# OZ440-SE100-CAR003_sheet8.net
KiCad netlist of a schematic drawn in Altium Designer
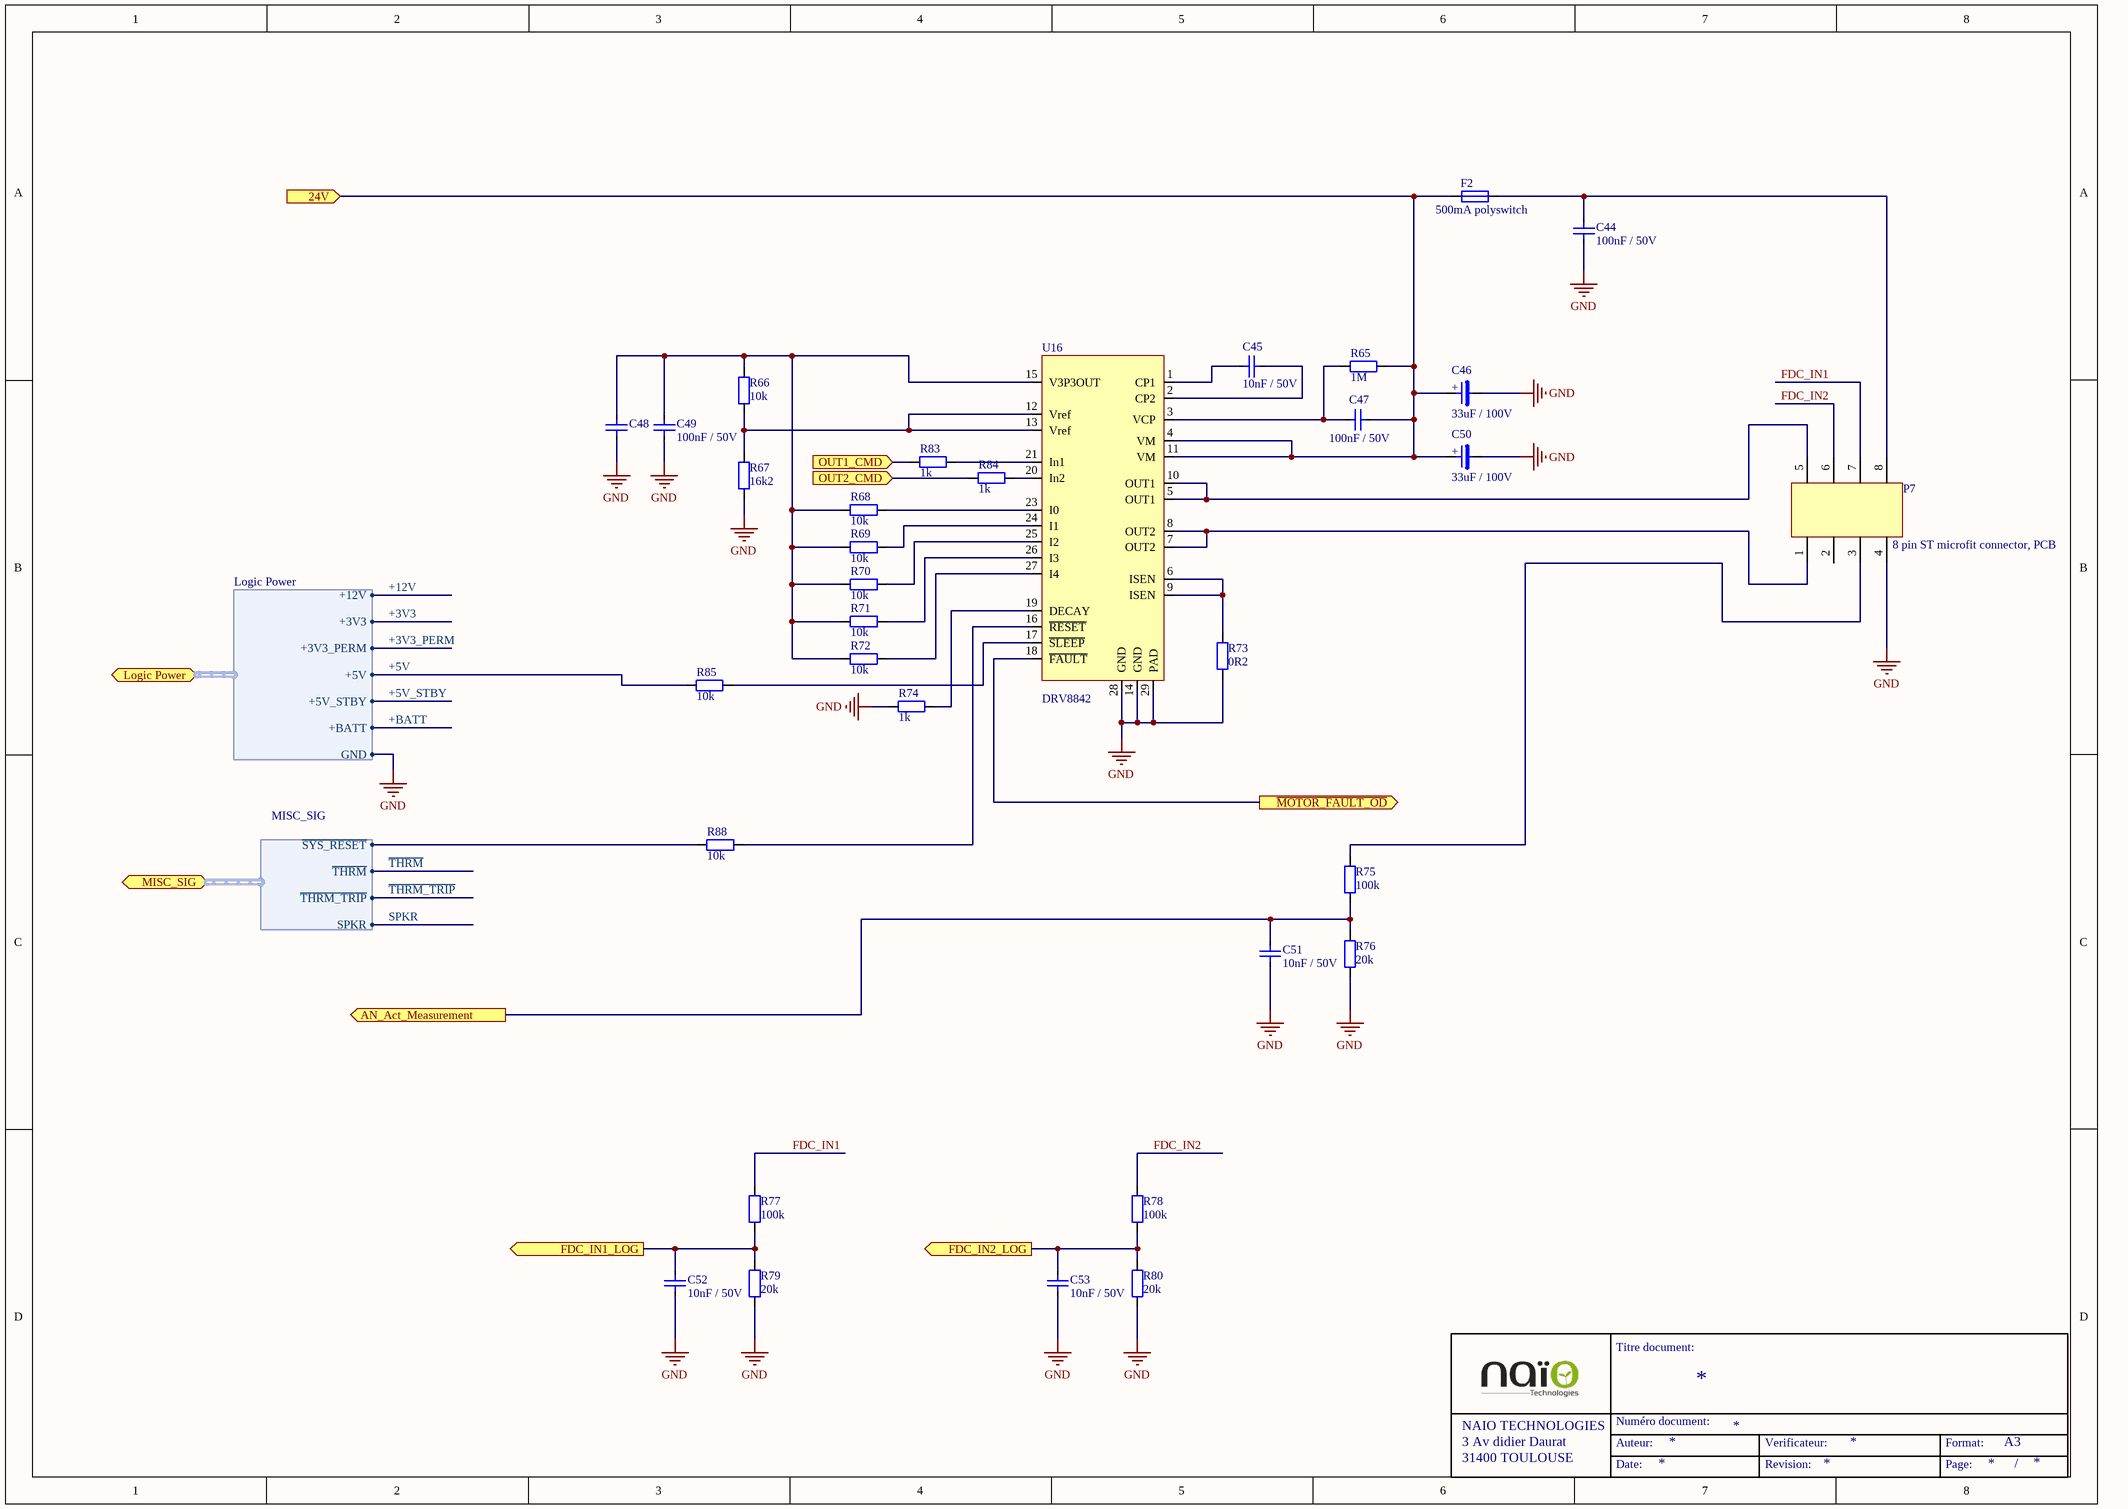
[diagram p0: OZ440-SE100-CAR003_sheet8.SchDoc]

(export (version "E")
  (design (tool "Eeschema 10.0.6"))
  (components
    (comp (ref "C44")
      (value "CAP-SMD")
      (footprint "C0805-STD")
      (description "0805 100nF / 50V  X7R ceramic capacitor")
      (fields
        (field (name "DISPLAYED REFERENCE") "100nF / 50V")
        (field (name "TOLERANCE") "+/- 10%")
        (field (name "MANUFACTURER") "vishay")
      )
      (libsource (lib "lib_NAIO") (part "CAP-SMD"))
    )
    (comp (ref "C45")
      (value "CAP-SMD")
      (footprint "C0805-STD")
      (description "0805 10nF / 50V X7R ceramic capacitor")
      (fields
        (field (name "DISPLAYED REFERENCE") "10nF / 50V")
        (field (name "TOLERANCE") "+/- 10%")
        (field (name "MANUFACTURER") "vishay")
      )
      (libsource (lib "lib_NAIO") (part "CAP-SMD"))
    )
    (comp (ref "C46")
      (value "CAP-POL-SMD")
      (footprint "CAP-ELECTRO-SMD_SIZE_G")
      (description "33uF / 100V Aluminium capacitor SMD")
      (fields (field (name "DISPLAYED REFERENCE") "33uF / 100V") (field (name "MANUFACTURER") "Panasonic"))
      (libsource (lib "lib_NAIO") (part "CAP-POL-SMD"))
    )
    (comp (ref "C47")
      (value "CAP-SMD")
      (footprint "C0805-STD")
      (description "0805 100nF / 50V  X7R ceramic capacitor")
      (fields
        (field (name "DISPLAYED REFERENCE") "100nF / 50V")
        (field (name "TOLERANCE") "+/- 10%")
        (field (name "MANUFACTURER") "vishay")
      )
      (libsource (lib "lib_NAIO") (part "CAP-SMD"))
    )
    (comp (ref "C48")
      (value "CAP-SMD")
      (footprint "C0805-STD")
      (description "0805 100nF / 50V  X7R ceramic capacitor")
      (fields (field (name "TOLERANCE") "+/- 10%") (field (name "MANUFACTURER") "vishay"))
      (libsource (lib "lib_NAIO") (part "CAP-SMD"))
    )
    (comp (ref "C49")
      (value "CAP-SMD")
      (footprint "C0805-STD")
      (description "0805 100nF / 50V  X7R ceramic capacitor")
      (fields
        (field (name "DISPLAYED REFERENCE") "100nF / 50V")
        (field (name "TOLERANCE") "+/- 10%")
        (field (name "MANUFACTURER") "vishay")
      )
      (libsource (lib "lib_NAIO") (part "CAP-SMD"))
    )
    (comp (ref "C50")
      (value "CAP-POL-SMD")
      (footprint "CAP-ELECTRO-SMD_SIZE_G")
      (description "33uF / 100V Aluminium capacitor SMD")
      (fields (field (name "DISPLAYED REFERENCE") "33uF / 100V") (field (name "MANUFACTURER") "Panasonic"))
      (libsource (lib "lib_NAIO") (part "CAP-POL-SMD"))
    )
    (comp (ref "C51")
      (value "CAP-SMD")
      (footprint "C0805-STD")
      (description "0805 10nF / 50V X7R ceramic capacitor")
      (fields
        (field (name "DISPLAYED REFERENCE") "10nF / 50V")
        (field (name "TOLERANCE") "+/- 10%")
        (field (name "MANUFACTURER") "vishay")
      )
      (libsource (lib "lib_NAIO") (part "CAP-SMD"))
    )
    (comp (ref "C52")
      (value "CAP-SMD")
      (footprint "C0805-STD")
      (description "0805 10nF / 50V X7R ceramic capacitor")
      (fields
        (field (name "DISPLAYED REFERENCE") "10nF / 50V")
        (field (name "TOLERANCE") "+/- 10%")
        (field (name "MANUFACTURER") "vishay")
      )
      (libsource (lib "lib_NAIO") (part "CAP-SMD"))
    )
    (comp (ref "C53")
      (value "CAP-SMD")
      (footprint "C0805-STD")
      (description "0805 10nF / 50V X7R ceramic capacitor")
      (fields
        (field (name "DISPLAYED REFERENCE") "10nF / 50V")
        (field (name "TOLERANCE") "+/- 10%")
        (field (name "MANUFACTURER") "vishay")
      )
      (libsource (lib "lib_NAIO") (part "CAP-SMD"))
    )
    (comp (ref "F2")
      (value "FUSE-SMD")
      (footprint "R0805-STD")
      (description "0805 500mA resettable fuse")
      (fields (field (name "DISPLAYED REFERENCE") "500mA polyswitch") (field (name "MANUFACTURER") "BOURNS"))
      (libsource (lib "lib_NAIO") (part "FUSE-SMD"))
    )
    (comp (ref "P7")
      (value "CONN-SPE-8P_MOLEX_43045-0801")
      (footprint "CONN-SPE_MOLEX_43045-0812")
      (description "8 pin Microfit connector")
      (fields
        (field (name "DISPLAYED REFERENCE") "8 pin ST microfit connector, PCB")
        (field (name "MANUFACTURER") "Molex")
      )
      (libsource (lib "lib_NAIO") (part "CONN-SPE-8P_MOLEX_43045-0801"))
    )
    (comp (ref "R65")
      (value "RES-SMD")
      (footprint "R0805-STD")
      (description "1Mohm 1% 0805 SMD resistor")
      (fields
        (field (name "DISPLAYED REFERENCE") "1M")
        (field (name "TOLERANCE") "1%")
        (field (name "MANUFACTURER") "Vishay")
      )
      (libsource (lib "") (part "RES-SMD_1"))
    )
    (comp (ref "R66")
      (value "RES-SMD")
      (footprint "R0805-STD")
      (description "10k Ohm 0805 SMD resistor")
      (fields
        (field (name "DISPLAYED REFERENCE") "10k")
        (field (name "TOLERANCE") "1 %")
        (field (name "MANUFACTURER") "Vishay")
      )
      (libsource (lib "") (part "RES-SMD_2"))
    )
    (comp (ref "R67")
      (value "RES-SMD")
      (footprint "R0805-STD")
      (description "16k2 Ohm 0805 SMD resistor")
      (fields
        (field (name "DISPLAYED REFERENCE") "16k2")
        (field (name "TOLERANCE") "1%")
        (field (name "MANUFACTURER") "Vishay")
      )
      (libsource (lib "lib_NAIO") (part "RES-SMD"))
    )
    (comp (ref "R68")
      (value "RES-SMD")
      (footprint "R0805-STD")
      (description "10k Ohm 0805 SMD resistor")
      (fields
        (field (name "DISPLAYED REFERENCE") "10k")
        (field (name "TOLERANCE") "1 %")
        (field (name "MANUFACTURER") "Vishay")
      )
      (libsource (lib "") (part "RES-SMD_1"))
    )
    (comp (ref "R69")
      (value "RES-SMD")
      (footprint "R0805-STD")
      (description "10k Ohm 0805 SMD resistor")
      (fields
        (field (name "DISPLAYED REFERENCE") "10k")
        (field (name "TOLERANCE") "1 %")
        (field (name "MANUFACTURER") "Vishay")
      )
      (libsource (lib "") (part "RES-SMD_1"))
    )
    (comp (ref "R70")
      (value "RES-SMD")
      (footprint "R0805-STD")
      (description "10k Ohm 0805 SMD resistor")
      (fields
        (field (name "DISPLAYED REFERENCE") "10k")
        (field (name "TOLERANCE") "1 %")
        (field (name "MANUFACTURER") "Vishay")
      )
      (libsource (lib "") (part "RES-SMD_1"))
    )
    (comp (ref "R71")
      (value "RES-SMD")
      (footprint "R0805-STD")
      (description "10k Ohm 0805 SMD resistor")
      (fields
        (field (name "DISPLAYED REFERENCE") "10k")
        (field (name "TOLERANCE") "1 %")
        (field (name "MANUFACTURER") "Vishay")
      )
      (libsource (lib "") (part "RES-SMD_1"))
    )
    (comp (ref "R72")
      (value "RES-SMD")
      (footprint "R0805-STD")
      (description "10k Ohm 0805 SMD resistor")
      (fields
        (field (name "DISPLAYED REFERENCE") "10k")
        (field (name "TOLERANCE") "1 %")
        (field (name "MANUFACTURER") "Vishay")
      )
      (libsource (lib "") (part "RES-SMD_1"))
    )
    (comp (ref "R73")
      (value "RES-SMD")
      (footprint "R2512-STD")
      (description "0.2R 1% 2512 SMD resistor")
      (fields
        (field (name "DISPLAYED REFERENCE") "0R2")
        (field (name "TOLERANCE") "1%")
        (field (name "MANUFACTURER") "Bourns")
      )
      (libsource (lib "lib_NAIO") (part "RES-SMD"))
    )
    (comp (ref "R74")
      (value "RES-SMD")
      (footprint "R0805-STD")
      (description "1k Ohm 0805 SMD resistor")
      (fields
        (field (name "DISPLAYED REFERENCE") "1k")
        (field (name "TOLERANCE") "1 %")
        (field (name "MANUFACTURER") "Vishay")
      )
      (libsource (lib "") (part "RES-SMD_1"))
    )
    (comp (ref "R75")
      (value "RES-SMD")
      (footprint "R0805-STD")
      (description "100k Ohm 0805 SMD resistor")
      (fields
        (field (name "DISPLAYED REFERENCE") "100k")
        (field (name "TOLERANCE") "1 %")
        (field (name "MANUFACTURER") "Vishay")
      )
      (libsource (lib "lib_NAIO") (part "RES-SMD"))
    )
    (comp (ref "R76")
      (value "RES-SMD")
      (footprint "R0805-STD")
      (description "20k Ohm 0805 SMD resistor")
      (fields
        (field (name "DISPLAYED REFERENCE") "20k")
        (field (name "TOLERANCE") "1 %")
        (field (name "MANUFACTURER") "Vishay")
      )
      (libsource (lib "lib_NAIO") (part "RES-SMD"))
    )
    (comp (ref "R77")
      (value "RES-SMD")
      (footprint "R0805-STD")
      (description "100k Ohm 0805 SMD resistor")
      (fields
        (field (name "DISPLAYED REFERENCE") "100k")
        (field (name "TOLERANCE") "1 %")
        (field (name "MANUFACTURER") "Vishay")
      )
      (libsource (lib "lib_NAIO") (part "RES-SMD"))
    )
    (comp (ref "R78")
      (value "RES-SMD")
      (footprint "R0805-STD")
      (description "100k Ohm 0805 SMD resistor")
      (fields
        (field (name "DISPLAYED REFERENCE") "100k")
        (field (name "TOLERANCE") "1 %")
        (field (name "MANUFACTURER") "Vishay")
      )
      (libsource (lib "lib_NAIO") (part "RES-SMD"))
    )
    (comp (ref "R79")
      (value "RES-SMD")
      (footprint "R0805-STD")
      (description "20k Ohm 0805 SMD resistor")
      (fields
        (field (name "DISPLAYED REFERENCE") "20k")
        (field (name "TOLERANCE") "1 %")
        (field (name "MANUFACTURER") "Vishay")
      )
      (libsource (lib "lib_NAIO") (part "RES-SMD"))
    )
    (comp (ref "R80")
      (value "RES-SMD")
      (footprint "R0805-STD")
      (description "20k Ohm 0805 SMD resistor")
      (fields
        (field (name "DISPLAYED REFERENCE") "20k")
        (field (name "TOLERANCE") "1 %")
        (field (name "MANUFACTURER") "Vishay")
      )
      (libsource (lib "lib_NAIO") (part "RES-SMD"))
    )
    (comp (ref "R83")
      (value "RES-SMD")
      (footprint "R0805-STD")
      (description "1k Ohm 0805 SMD resistor")
      (fields
        (field (name "DISPLAYED REFERENCE") "1k")
        (field (name "TOLERANCE") "1 %")
        (field (name "MANUFACTURER") "Vishay")
      )
      (libsource (lib "") (part "RES-SMD_1"))
    )
    (comp (ref "R84")
      (value "RES-SMD")
      (footprint "R0805-STD")
      (description "1k Ohm 0805 SMD resistor")
      (fields
        (field (name "DISPLAYED REFERENCE") "1k")
        (field (name "TOLERANCE") "1 %")
        (field (name "MANUFACTURER") "Vishay")
      )
      (libsource (lib "") (part "RES-SMD_1"))
    )
    (comp (ref "R85")
      (value "RES-SMD")
      (footprint "R0805-STD")
      (description "10k Ohm 0805 SMD resistor")
      (fields
        (field (name "DISPLAYED REFERENCE") "10k")
        (field (name "TOLERANCE") "1 %")
        (field (name "MANUFACTURER") "Vishay")
      )
      (libsource (lib "") (part "RES-SMD_1"))
    )
    (comp (ref "R88")
      (value "RES-SMD")
      (footprint "R0805-STD")
      (description "10k Ohm 0805 SMD resistor")
      (fields
        (field (name "DISPLAYED REFERENCE") "10k")
        (field (name "TOLERANCE") "1 %")
        (field (name "MANUFACTURER") "Vishay")
      )
      (libsource (lib "") (part "RES-SMD_1"))
    )
    (comp (ref "U16")
      (value "DRV8842-TSSOP28")
      (footprint "TSSOP28-SPE-DRV8842")
      (description "DC MOTOR DRIVER IC")
      (fields (field (name "DISPLAYED REFERENCE") "DRV8842") (field (name "MANUFACTURER") "TI"))
      (libsource (lib "lib_NAIO") (part "DRV8842-TSSOP28"))
    )
  )
  (nets
    (net (code "6") (name "/+5V") (class "Default")
      (node (ref "R85") (pin "1") (pinfunction "1_1") (pintype "passive"))
    )
    (net (code "10") (name "/24V") (class "Default")
      (node (ref "C46") (pin "1") (pinfunction "1_1") (pintype "passive"))
      (node (ref "C47") (pin "2") (pinfunction "2_2") (pintype "passive"))
      (node (ref "C50") (pin "1") (pinfunction "1_1") (pintype "passive"))
      (node (ref "F2") (pin "1") (pinfunction "1_1") (pintype "passive"))
      (node (ref "R65") (pin "2") (pinfunction "2_2") (pintype "passive"))
      (node (ref "U16") (pin "11") (pinfunction "VM_11") (pintype "passive"))
      (node (ref "U16") (pin "4") (pinfunction "VM_4") (pintype "passive"))
    )
    (net (code "11") (name "/AN_Act_Measurement") (class "Default")
      (node (ref "C51") (pin "2") (pinfunction "2_2") (pintype "passive"))
      (node (ref "R75") (pin "1") (pinfunction "1_1") (pintype "passive"))
      (node (ref "R76") (pin "2") (pinfunction "2_2") (pintype "passive"))
    )
    (net (code "12") (name "/FDC_IN1") (class "Default")
      (node (ref "P7") (pin "7") (pinfunction "7_7") (pintype "passive"))
      (node (ref "R77") (pin "2") (pinfunction "2_2") (pintype "passive"))
    )
    (net (code "13") (name "/FDC_IN1_LOG") (class "Default")
      (node (ref "C52") (pin "2") (pinfunction "2_2") (pintype "passive"))
      (node (ref "R77") (pin "1") (pinfunction "1_1") (pintype "passive"))
      (node (ref "R79") (pin "2") (pinfunction "2_2") (pintype "passive"))
    )
    (net (code "14") (name "/FDC_IN2") (class "Default")
      (node (ref "P7") (pin "6") (pinfunction "6_6") (pintype "passive"))
      (node (ref "R78") (pin "2") (pinfunction "2_2") (pintype "passive"))
    )
    (net (code "15") (name "/FDC_IN2_LOG") (class "Default")
      (node (ref "C53") (pin "2") (pinfunction "2_2") (pintype "passive"))
      (node (ref "R78") (pin "1") (pinfunction "1_1") (pintype "passive"))
      (node (ref "R80") (pin "2") (pinfunction "2_2") (pintype "passive"))
    )
    (net (code "16") (name "/MOTOR_FAULT_OD") (class "Default")
      (node (ref "U16") (pin "18") (pinfunction "FAULT_18") (pintype "passive"))
    )
    (net (code "17") (name "/OUT1_CMD") (class "Default")
      (node (ref "R83") (pin "1") (pinfunction "1_1") (pintype "passive"))
    )
    (net (code "18") (name "/OUT2_CMD") (class "Default")
      (node (ref "R84") (pin "1") (pinfunction "1_1") (pintype "passive"))
    )
    (net (code "24") (name "/~{SYS_RESET}") (class "Default")
      (node (ref "R88") (pin "1") (pinfunction "1_1") (pintype "passive"))
    )
    (net (code "25") (name "GND") (class "Default")
      (node (ref "C44") (pin "1") (pinfunction "1_1") (pintype "passive"))
      (node (ref "C46") (pin "2") (pinfunction "2_2") (pintype "passive"))
      (node (ref "C48") (pin "1") (pinfunction "1_1") (pintype "passive"))
      (node (ref "C49") (pin "1") (pinfunction "1_1") (pintype "passive"))
      (node (ref "C50") (pin "2") (pinfunction "2_2") (pintype "passive"))
      (node (ref "C51") (pin "1") (pinfunction "1_1") (pintype "passive"))
      (node (ref "C52") (pin "1") (pinfunction "1_1") (pintype "passive"))
      (node (ref "C53") (pin "1") (pinfunction "1_1") (pintype "passive"))
      (node (ref "P7") (pin "4") (pinfunction "7_4") (pintype "passive"))
      (node (ref "R67") (pin "1") (pinfunction "1_1") (pintype "passive"))
      (node (ref "R73") (pin "1") (pinfunction "1_1") (pintype "passive"))
      (node (ref "R74") (pin "1") (pinfunction "1_1") (pintype "passive"))
      (node (ref "R76") (pin "1") (pinfunction "1_1") (pintype "passive"))
      (node (ref "R79") (pin "1") (pinfunction "1_1") (pintype "passive"))
      (node (ref "R80") (pin "1") (pinfunction "1_1") (pintype "passive"))
      (node (ref "U16") (pin "14") (pinfunction "GND_14") (pintype "passive"))
      (node (ref "U16") (pin "28") (pinfunction "GND_28") (pintype "passive"))
      (node (ref "U16") (pin "29") (pinfunction "PAD_29") (pintype "passive"))
    )
    (net (code "26") (name "Net-(C44-Pad2)") (class "Default")
      (node (ref "C44") (pin "2") (pinfunction "2_2") (pintype "passive"))
      (node (ref "F2") (pin "2") (pinfunction "2_2") (pintype "passive"))
      (node (ref "P7") (pin "8") (pinfunction "8_8") (pintype "passive"))
    )
    (net (code "27") (name "Net-(P7-9)") (class "Default")
      (node (ref "P7") (pin "5") (pinfunction "9_5") (pintype "passive"))
      (node (ref "U16") (pin "10") (pinfunction "OUT1_10") (pintype "passive"))
      (node (ref "U16") (pin "5") (pinfunction "OUT1_5") (pintype "passive"))
    )
    (net (code "28") (name "Net-(P7-Pad1)") (class "Default")
      (node (ref "P7") (pin "1") (pinfunction "1_1") (pintype "passive"))
      (node (ref "U16") (pin "7") (pinfunction "OUT2_7") (pintype "passive"))
      (node (ref "U16") (pin "8") (pinfunction "OUT2_8") (pintype "passive"))
    )
    (net (code "29") (name "Net-(P7-Pad3)") (class "Default")
      (node (ref "P7") (pin "3") (pinfunction "3_3") (pintype "passive"))
      (node (ref "R75") (pin "2") (pinfunction "2_2") (pintype "passive"))
    )
    (net (code "30") (name "Net-(R66-Pad2)") (class "Default")
      (node (ref "R66") (pin "2") (pinfunction "2_2") (pintype "passive"))
      (node (ref "R67") (pin "2") (pinfunction "2_2") (pintype "passive"))
      (node (ref "U16") (pin "12") (pinfunction "Vref_12") (pintype "passive"))
      (node (ref "U16") (pin "13") (pinfunction "Vref_13") (pintype "passive"))
    )
    (net (code "31") (name "Net-(R73-Pad2)") (class "Default")
      (node (ref "R73") (pin "2") (pinfunction "2_2") (pintype "passive"))
      (node (ref "U16") (pin "6") (pinfunction "ISEN_6") (pintype "passive"))
      (node (ref "U16") (pin "9") (pinfunction "ISEN_9") (pintype "passive"))
    )
    (net (code "32") (name "Net-(U16-CP1)") (class "Default")
      (node (ref "C45") (pin "1") (pinfunction "1_1") (pintype "passive"))
      (node (ref "U16") (pin "1") (pinfunction "CP1_1") (pintype "passive"))
    )
    (net (code "33") (name "Net-(U16-CP2)") (class "Default")
      (node (ref "C45") (pin "2") (pinfunction "2_2") (pintype "passive"))
      (node (ref "U16") (pin "2") (pinfunction "CP2_2") (pintype "passive"))
    )
    (net (code "34") (name "Net-(U16-DECAY)") (class "Default")
      (node (ref "R74") (pin "2") (pinfunction "2_2") (pintype "passive"))
      (node (ref "U16") (pin "19") (pinfunction "DECAY_19") (pintype "passive"))
    )
    (net (code "35") (name "Net-(U16-I0)") (class "Default")
      (node (ref "R68") (pin "2") (pinfunction "2_2") (pintype "passive"))
      (node (ref "U16") (pin "23") (pinfunction "I0_23") (pintype "passive"))
    )
    (net (code "36") (name "Net-(U16-I1)") (class "Default")
      (node (ref "R69") (pin "2") (pinfunction "2_2") (pintype "passive"))
      (node (ref "U16") (pin "24") (pinfunction "I1_24") (pintype "passive"))
    )
    (net (code "37") (name "Net-(U16-I2)") (class "Default")
      (node (ref "R70") (pin "2") (pinfunction "2_2") (pintype "passive"))
      (node (ref "U16") (pin "25") (pinfunction "I2_25") (pintype "passive"))
    )
    (net (code "38") (name "Net-(U16-I3)") (class "Default")
      (node (ref "R71") (pin "2") (pinfunction "2_2") (pintype "passive"))
      (node (ref "U16") (pin "26") (pinfunction "I3_26") (pintype "passive"))
    )
    (net (code "39") (name "Net-(U16-I4)") (class "Default")
      (node (ref "R72") (pin "2") (pinfunction "2_2") (pintype "passive"))
      (node (ref "U16") (pin "27") (pinfunction "I4_27") (pintype "passive"))
    )
    (net (code "40") (name "Net-(U16-In1)") (class "Default")
      (node (ref "R83") (pin "2") (pinfunction "2_2") (pintype "passive"))
      (node (ref "U16") (pin "21") (pinfunction "In1_21") (pintype "passive"))
    )
    (net (code "41") (name "Net-(U16-In2)") (class "Default")
      (node (ref "R84") (pin "2") (pinfunction "2_2") (pintype "passive"))
      (node (ref "U16") (pin "20") (pinfunction "In2_20") (pintype "passive"))
    )
    (net (code "42") (name "Net-(U16-RESET)") (class "Default")
      (node (ref "R88") (pin "2") (pinfunction "2_2") (pintype "passive"))
      (node (ref "U16") (pin "16") (pinfunction "RESET_16") (pintype "passive"))
    )
    (net (code "43") (name "Net-(U16-SLEEP)") (class "Default")
      (node (ref "R85") (pin "2") (pinfunction "2_2") (pintype "passive"))
      (node (ref "U16") (pin "17") (pinfunction "SLEEP_17") (pintype "passive"))
    )
    (net (code "44") (name "Net-(U16-V3P3OUT)") (class "Default")
      (node (ref "C48") (pin "2") (pinfunction "2_2") (pintype "passive"))
      (node (ref "C49") (pin "2") (pinfunction "2_2") (pintype "passive"))
      (node (ref "R66") (pin "1") (pinfunction "1_1") (pintype "passive"))
      (node (ref "R68") (pin "1") (pinfunction "1_1") (pintype "passive"))
      (node (ref "R69") (pin "1") (pinfunction "1_1") (pintype "passive"))
      (node (ref "R70") (pin "1") (pinfunction "1_1") (pintype "passive"))
      (node (ref "R71") (pin "1") (pinfunction "1_1") (pintype "passive"))
      (node (ref "R72") (pin "1") (pinfunction "1_1") (pintype "passive"))
      (node (ref "U16") (pin "15") (pinfunction "V3P3OUT_15") (pintype "passive"))
    )
    (net (code "45") (name "Net-(U16-VCP)") (class "Default")
      (node (ref "C47") (pin "1") (pinfunction "1_1") (pintype "passive"))
      (node (ref "R65") (pin "1") (pinfunction "1_1") (pintype "passive"))
      (node (ref "U16") (pin "3") (pinfunction "VCP_3") (pintype "passive"))
    )
    (net (code "46") (name "unconnected-(P7-Pad2)") (class "Default")
      (node (ref "P7") (pin "2") (pinfunction "2_2") (pintype "passive"))
    )
  )
)
